# Amplifier_Filter.net
KiCad netlist of a schematic drawn in Altium Designer
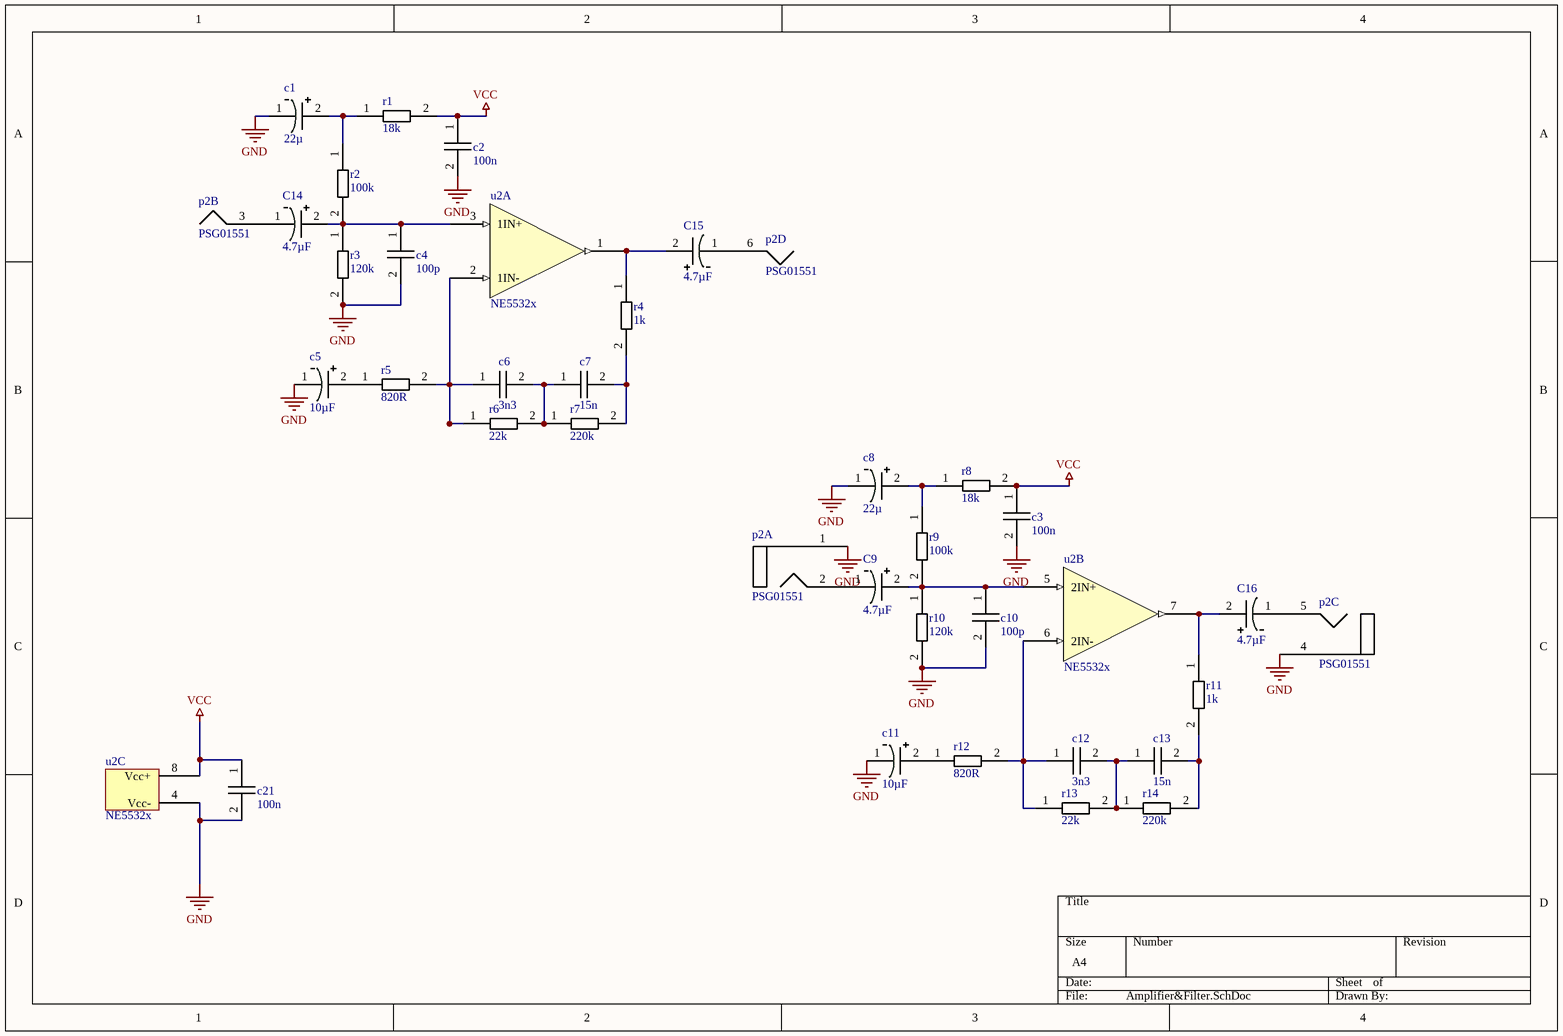
[diagram p0: Amplifier&Filter.SchDoc]

(export (version "E")
  (design (tool "Eeschema 10.0.6"))
  (components
    (comp (ref "c1")
      (value "22µ")
      (footprint "Elco-D")
      (description "Elco size D 6.3x5.4")
      (libsource (lib "Panasonic") (part "Elco D"))
    )
    (comp (ref "c2")
      (value "100n")
      (footprint "1206")
      (description "0805 Capacitor Package")
      (libsource (lib "Generic R-C") (part "0805 Capacitor"))
    )
    (comp (ref "c3")
      (value "100n")
      (footprint "1206")
      (description "0805 Capacitor Package")
      (libsource (lib "") (part "0805 Capacitor_1"))
    )
    (comp (ref "c4")
      (value "100p")
      (footprint "1206")
      (description "Capacitor package 1206")
      (libsource (lib "Generic R-C") (part "1206 Cap"))
    )
    (comp (ref "c5") (value "10µF") (footprint "Elco-C") (libsource (lib "Panasonic") (part "Elco C")))
    (comp (ref "c6")
      (value "3n3")
      (footprint "1206")
      (description "Capacitor package 1206")
      (libsource (lib "Generic R-C") (part "1206 Cap"))
    )
    (comp (ref "c7")
      (value "15n")
      (footprint "1206")
      (description "Capacitor package 1206")
      (libsource (lib "Generic R-C") (part "1206 Cap"))
    )
    (comp (ref "c8")
      (value "22µ")
      (footprint "Elco-D")
      (description "Elco size D 6.3x5.4")
      (libsource (lib "Panasonic") (part "Elco D"))
    )
    (comp (ref "C9") (value "4.7µF") (footprint "Elco-C") (libsource (lib "Panasonic") (part "Elco C")))
    (comp (ref "c10")
      (value "100p")
      (footprint "1206")
      (description "Capacitor package 1206")
      (libsource (lib "Generic R-C") (part "1206 Cap"))
    )
    (comp (ref "c11") (value "10µF") (footprint "Elco-C") (libsource (lib "Panasonic") (part "Elco C")))
    (comp (ref "c12")
      (value "3n3")
      (footprint "1206")
      (description "Capacitor package 1206")
      (libsource (lib "Generic R-C") (part "1206 Cap"))
    )
    (comp (ref "c13")
      (value "15n")
      (footprint "1206")
      (description "Capacitor package 1206")
      (libsource (lib "Generic R-C") (part "1206 Cap"))
    )
    (comp (ref "C14") (value "4.7µF") (footprint "Elco-C") (libsource (lib "Panasonic") (part "Elco C")))
    (comp (ref "C15") (value "4.7µF") (footprint "Elco-C") (libsource (lib "Panasonic") (part "Elco C")))
    (comp (ref "C16") (value "4.7µF") (footprint "Elco-C") (libsource (lib "Panasonic") (part "Elco C")))
    (comp (ref "c21")
      (value "100n")
      (footprint "0805")
      (description "0805 Capacitor Package")
      (libsource (lib "Generic R-C") (part "0805 Capacitor"))
    )
    (comp (ref "p2")
      (value "PSG01551")
      (footprint "RCA 4-way")
      (description "4-way RCA connector")
      (libsource (lib "Pro-Signal") (part "PSG01551"))
    )
    (comp (ref "r1")
      (value "18k")
      (footprint "1206")
      (description "Resistor Package 1206")
      (libsource (lib "Generic R-C") (part "1206 Resistor"))
    )
    (comp (ref "r2")
      (value "100k")
      (footprint "1206")
      (description "Resistor Package 1206")
      (libsource (lib "Generic R-C") (part "1206 Resistor"))
    )
    (comp (ref "r3")
      (value "120k")
      (footprint "1206")
      (description "Resistor Package 1206")
      (libsource (lib "Generic R-C") (part "1206 Resistor"))
    )
    (comp (ref "r4")
      (value "1k")
      (footprint "1206")
      (description "Resistor Package 1206")
      (libsource (lib "Generic R-C") (part "1206 Resistor"))
    )
    (comp (ref "r5")
      (value "820R")
      (footprint "1206")
      (description "Resistor Package 1206")
      (libsource (lib "Generic R-C") (part "1206 Resistor"))
    )
    (comp (ref "r6")
      (value "22k")
      (footprint "1206")
      (description "Resistor Package 1206")
      (libsource (lib "Generic R-C") (part "1206 Resistor"))
    )
    (comp (ref "r7")
      (value "220k")
      (footprint "1206")
      (description "Resistor Package 1206")
      (libsource (lib "Generic R-C") (part "1206 Resistor"))
    )
    (comp (ref "r8")
      (value "18k")
      (footprint "1206")
      (description "Resistor Package 1206")
      (libsource (lib "Generic R-C") (part "1206 Resistor"))
    )
    (comp (ref "r9")
      (value "100k")
      (footprint "1206")
      (description "Resistor Package 1206")
      (libsource (lib "Generic R-C") (part "1206 Resistor"))
    )
    (comp (ref "r10")
      (value "120k")
      (footprint "1206")
      (description "Resistor Package 1206")
      (libsource (lib "Generic R-C") (part "1206 Resistor"))
    )
    (comp (ref "r11")
      (value "1k")
      (footprint "1206")
      (description "Resistor Package 1206")
      (libsource (lib "Generic R-C") (part "1206 Resistor"))
    )
    (comp (ref "r12")
      (value "820R")
      (footprint "1206")
      (description "Resistor Package 1206")
      (libsource (lib "Generic R-C") (part "1206 Resistor"))
    )
    (comp (ref "r13")
      (value "22k")
      (footprint "1206")
      (description "Resistor Package 1206")
      (libsource (lib "Generic R-C") (part "1206 Resistor"))
    )
    (comp (ref "r14")
      (value "220k")
      (footprint "1206")
      (description "Resistor Package 1206")
      (libsource (lib "Generic R-C") (part "1206 Resistor"))
    )
    (comp (ref "u2")
      (value "NE5532x")
      (footprint "R-PDSO-G8-P127d620x530")
      (description "Dual Low-Noise OpAmp")
      (libsource (lib "Texas Instruments") (part "NE5532x"))
    )
  )
  (nets
    (net (code "1") (name "GND") (class "Default")
      (node (ref "c1") (pin "1") (pintype "passive"))
      (node (ref "c10") (pin "2") (pintype "passive"))
      (node (ref "c11") (pin "1") (pintype "passive"))
      (node (ref "c2") (pin "2") (pintype "passive"))
      (node (ref "c21") (pin "2") (pintype "passive"))
      (node (ref "c3") (pin "2") (pintype "passive"))
      (node (ref "c4") (pin "2") (pintype "passive"))
      (node (ref "c5") (pin "1") (pintype "passive"))
      (node (ref "c8") (pin "1") (pintype "passive"))
      (node (ref "p2") (pin "1") (pintype "power_in"))
      (node (ref "p2") (pin "4") (pintype "power_in"))
      (node (ref "r10") (pin "2") (pintype "passive"))
      (node (ref "r3") (pin "2") (pintype "passive"))
      (node (ref "u2") (pin "4") (pinfunction "Vcc-_4") (pintype "power_in"))
    )
    (net (code "2") (name "Net-(C9-Pad1)") (class "Default")
      (node (ref "C9") (pin "1") (pintype "passive"))
      (node (ref "p2") (pin "2") (pintype "passive"))
    )
    (net (code "3") (name "Net-(C14-Pad1)") (class "Default")
      (node (ref "C14") (pin "1") (pintype "passive"))
      (node (ref "p2") (pin "3") (pintype "passive"))
    )
    (net (code "4") (name "Net-(C15-Pad1)") (class "Default")
      (node (ref "C15") (pin "1") (pintype "passive"))
      (node (ref "p2") (pin "6") (pintype "passive"))
    )
    (net (code "5") (name "Net-(C16-Pad1)") (class "Default")
      (node (ref "C16") (pin "1") (pintype "passive"))
      (node (ref "p2") (pin "5") (pintype "passive"))
    )
    (net (code "6") (name "Net-(c1-Pad2)") (class "Default")
      (node (ref "c1") (pin "2") (pintype "passive"))
      (node (ref "r1") (pin "1") (pintype "passive"))
      (node (ref "r2") (pin "1") (pintype "passive"))
    )
    (net (code "7") (name "Net-(c5-Pad2)") (class "Default")
      (node (ref "c5") (pin "2") (pintype "passive"))
      (node (ref "r5") (pin "1") (pintype "passive"))
    )
    (net (code "8") (name "Net-(c6-Pad2)") (class "Default")
      (node (ref "c6") (pin "2") (pintype "passive"))
      (node (ref "c7") (pin "1") (pintype "passive"))
      (node (ref "r6") (pin "2") (pintype "passive"))
      (node (ref "r7") (pin "1") (pintype "passive"))
    )
    (net (code "9") (name "Net-(c7-Pad2)") (class "Default")
      (node (ref "c7") (pin "2") (pintype "passive"))
      (node (ref "r4") (pin "2") (pintype "passive"))
      (node (ref "r7") (pin "2") (pintype "passive"))
    )
    (net (code "10") (name "Net-(c8-Pad2)") (class "Default")
      (node (ref "c8") (pin "2") (pintype "passive"))
      (node (ref "r8") (pin "1") (pintype "passive"))
      (node (ref "r9") (pin "1") (pintype "passive"))
    )
    (net (code "11") (name "Net-(c11-Pad2)") (class "Default")
      (node (ref "c11") (pin "2") (pintype "passive"))
      (node (ref "r12") (pin "1") (pintype "passive"))
    )
    (net (code "12") (name "Net-(c12-Pad2)") (class "Default")
      (node (ref "c12") (pin "2") (pintype "passive"))
      (node (ref "c13") (pin "1") (pintype "passive"))
      (node (ref "r13") (pin "2") (pintype "passive"))
      (node (ref "r14") (pin "1") (pintype "passive"))
    )
    (net (code "13") (name "Net-(c13-Pad2)") (class "Default")
      (node (ref "c13") (pin "2") (pintype "passive"))
      (node (ref "r11") (pin "2") (pintype "passive"))
      (node (ref "r14") (pin "2") (pintype "passive"))
    )
    (net (code "14") (name "Net-(u2A-1IN+)") (class "Default")
      (node (ref "C14") (pin "2") (pintype "passive"))
      (node (ref "c4") (pin "1") (pintype "passive"))
      (node (ref "r2") (pin "2") (pintype "passive"))
      (node (ref "r3") (pin "1") (pintype "passive"))
      (node (ref "u2") (pin "3") (pinfunction "1IN+_3") (pintype "input"))
    )
    (net (code "15") (name "Net-(u2A-1IN-)") (class "Default")
      (node (ref "c6") (pin "1") (pintype "passive"))
      (node (ref "r5") (pin "2") (pintype "passive"))
      (node (ref "r6") (pin "1") (pintype "passive"))
      (node (ref "u2") (pin "2") (pinfunction "1IN-_2") (pintype "input"))
    )
    (net (code "16") (name "Net-(u2A-1OUT)") (class "Default")
      (node (ref "C15") (pin "2") (pintype "passive"))
      (node (ref "r4") (pin "1") (pintype "passive"))
      (node (ref "u2") (pin "1") (pinfunction "1OUT_1") (pintype "output"))
    )
    (net (code "17") (name "Net-(u2B-2IN+)") (class "Default")
      (node (ref "C9") (pin "2") (pintype "passive"))
      (node (ref "c10") (pin "1") (pintype "passive"))
      (node (ref "r10") (pin "1") (pintype "passive"))
      (node (ref "r9") (pin "2") (pintype "passive"))
      (node (ref "u2") (pin "5") (pinfunction "2IN+_5") (pintype "input"))
    )
    (net (code "18") (name "Net-(u2B-2IN-)") (class "Default")
      (node (ref "c12") (pin "1") (pintype "passive"))
      (node (ref "r12") (pin "2") (pintype "passive"))
      (node (ref "r13") (pin "1") (pintype "passive"))
      (node (ref "u2") (pin "6") (pinfunction "2IN-_6") (pintype "input"))
    )
    (net (code "19") (name "Net-(u2B-2OUT)") (class "Default")
      (node (ref "C16") (pin "2") (pintype "passive"))
      (node (ref "r11") (pin "1") (pintype "passive"))
      (node (ref "u2") (pin "7") (pinfunction "2OUT_7") (pintype "output"))
    )
    (net (code "20") (name "VCC") (class "Default")
      (node (ref "c2") (pin "1") (pintype "passive"))
      (node (ref "c21") (pin "1") (pintype "passive"))
      (node (ref "c3") (pin "1") (pintype "passive"))
      (node (ref "r1") (pin "2") (pintype "passive"))
      (node (ref "r8") (pin "2") (pintype "passive"))
      (node (ref "u2") (pin "8") (pinfunction "Vcc+_8") (pintype "power_in"))
    )
  )
)
